# TLayerManager.net
KiCad netlist of a schematic drawn in Altium Designer
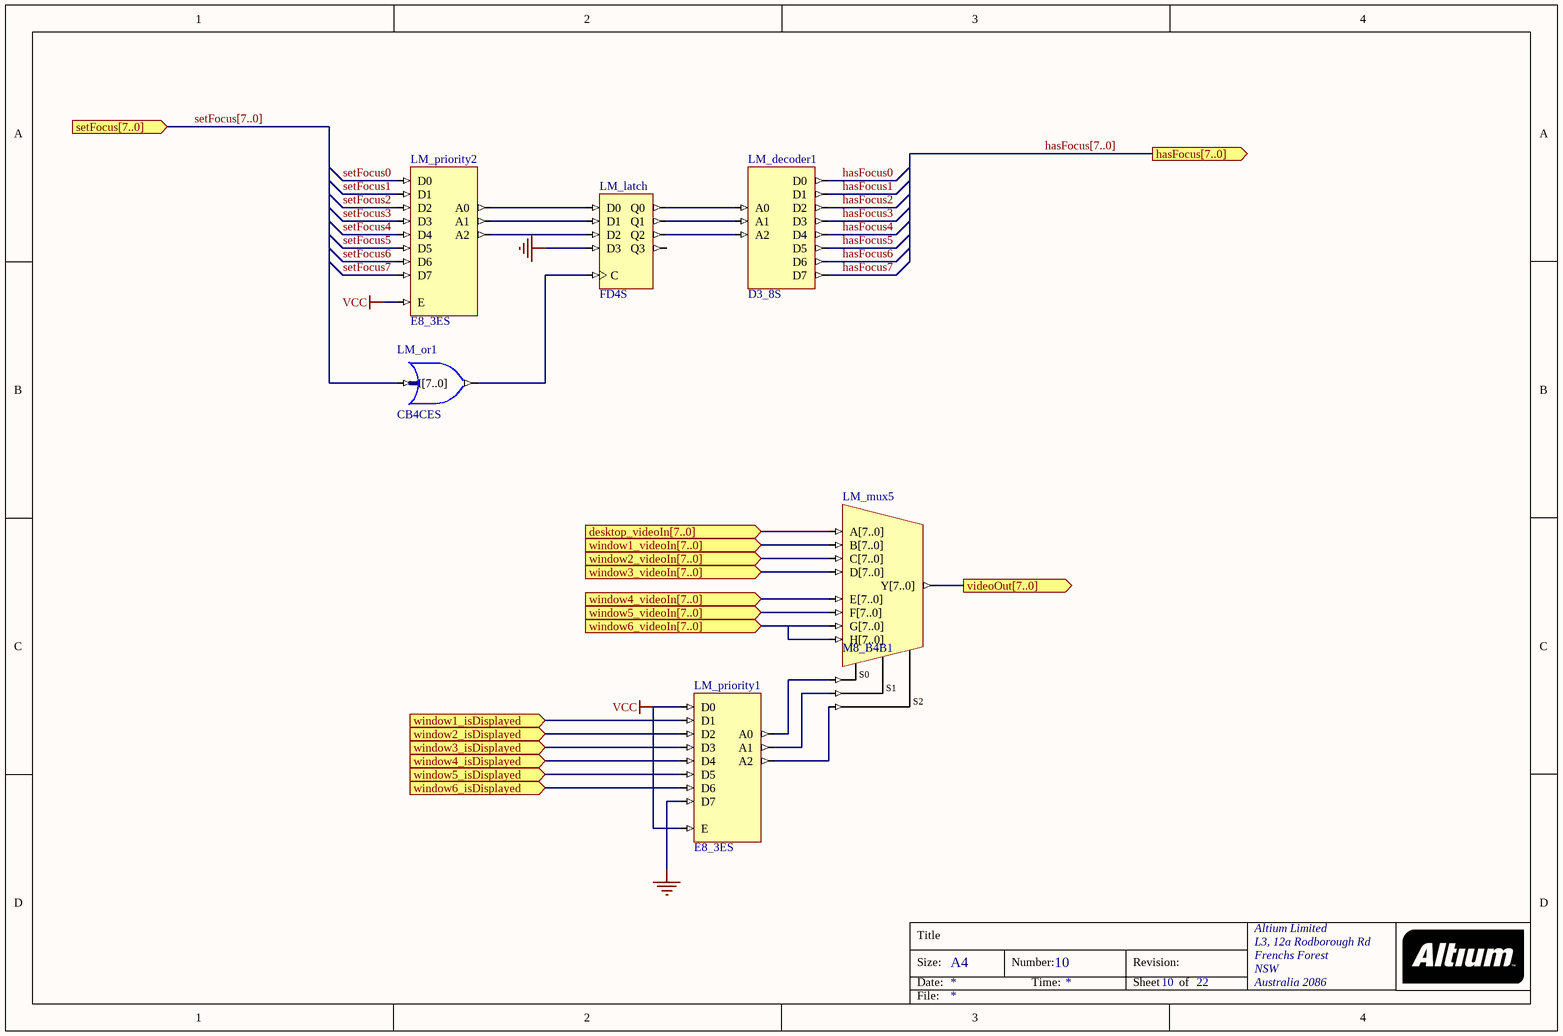
[diagram p0: TLayerManager.schDoc]

(export (version "E")
  (design (tool "Eeschema 10.0.6"))
  (components
    (comp (ref "LM_decoder1")
      (value "D3_8S")
      (description "Binary 3- to 8-Bit Decoder, Single Pin Version")
      (fields (field (name "PUBLISHER") "Altium Limited"))
      (libsource (lib "FPGA Generic") (part "D3_8S"))
    )
    (comp (ref "LM_latch")
      (value "FD4S")
      (description "4-Bit D-Type Flip-Flop, Single Pin Version")
      (fields (field (name "PUBLISHER") "Altium Limited"))
      (libsource (lib "FPGA Generic") (part "FD4S"))
    )
    (comp (ref "LM_mux5")
      (value "M8_B4B1")
      (description "8x8-Bit Bus to 1x8-Bit Bus Multiplexer")
      (fields (field (name "PUBLISHER") "Altium Limited"))
      (libsource (lib "FPGA Generic") (part "M8_B8B1"))
    )
    (comp (ref "LM_or1")
      (value "CB4CES")
      (description "8-Input OR Gate, Bus Version")
      (fields (field (name "PUBLISHER") "Altium Limited"))
      (libsource (lib "FPGA Generic") (part "OR8B"))
    )
    (comp (ref "LM_priority1")
      (value "E8_3ES")
      (description "8- to 3-Bit Priority Encoder with Enable, Single Pin Version")
      (fields (field (name "PUBLISHER") "Altium Limited"))
      (libsource (lib "FPGA Generic") (part "E8_3ES"))
    )
    (comp (ref "LM_priority2")
      (value "E8_3ES")
      (description "8- to 3-Bit Priority Encoder with Enable, Single Pin Version")
      (fields (field (name "PUBLISHER") "Altium Limited"))
      (libsource (lib "FPGA Generic") (part "E8_3ES"))
    )
  )
  (nets
    (net (code "65") (name "/desktop_videoIn[7..0]") (class "Default")
      (node (ref "LM_mux5") (pin "A[7..0]") (pinfunction "A[7..0]_A[7..0]") (pintype "input"))
    )
    (net (code "66") (name "/hasFocus0") (class "Default")
      (node (ref "LM_decoder1") (pin "D0") (pinfunction "D0_D0") (pintype "output"))
    )
    (net (code "67") (name "/hasFocus1") (class "Default")
      (node (ref "LM_decoder1") (pin "D1") (pinfunction "D1_D1") (pintype "output"))
    )
    (net (code "68") (name "/hasFocus2") (class "Default")
      (node (ref "LM_decoder1") (pin "D2") (pinfunction "D2_D2") (pintype "output"))
    )
    (net (code "69") (name "/hasFocus3") (class "Default")
      (node (ref "LM_decoder1") (pin "D3") (pinfunction "D3_D3") (pintype "output"))
    )
    (net (code "70") (name "/hasFocus4") (class "Default")
      (node (ref "LM_decoder1") (pin "D4") (pinfunction "D4_D4") (pintype "output"))
    )
    (net (code "71") (name "/hasFocus5") (class "Default")
      (node (ref "LM_decoder1") (pin "D5") (pinfunction "D5_D5") (pintype "output"))
    )
    (net (code "72") (name "/hasFocus6") (class "Default")
      (node (ref "LM_decoder1") (pin "D6") (pinfunction "D6_D6") (pintype "output"))
    )
    (net (code "73") (name "/hasFocus7") (class "Default")
      (node (ref "LM_decoder1") (pin "D7") (pinfunction "D7_D7") (pintype "output"))
    )
    (net (code "75") (name "/setFocus0") (class "Default")
      (node (ref "LM_priority2") (pin "D0") (pinfunction "D0_D0") (pintype "input"))
    )
    (net (code "76") (name "/setFocus1") (class "Default")
      (node (ref "LM_priority2") (pin "D1") (pinfunction "D1_D1") (pintype "input"))
    )
    (net (code "77") (name "/setFocus2") (class "Default")
      (node (ref "LM_priority2") (pin "D2") (pinfunction "D2_D2") (pintype "input"))
    )
    (net (code "78") (name "/setFocus3") (class "Default")
      (node (ref "LM_priority2") (pin "D3") (pinfunction "D3_D3") (pintype "input"))
    )
    (net (code "79") (name "/setFocus4") (class "Default")
      (node (ref "LM_priority2") (pin "D4") (pinfunction "D4_D4") (pintype "input"))
    )
    (net (code "80") (name "/setFocus5") (class "Default")
      (node (ref "LM_priority2") (pin "D5") (pinfunction "D5_D5") (pintype "input"))
    )
    (net (code "81") (name "/setFocus6") (class "Default")
      (node (ref "LM_priority2") (pin "D6") (pinfunction "D6_D6") (pintype "input"))
    )
    (net (code "82") (name "/setFocus7") (class "Default")
      (node (ref "LM_priority2") (pin "D7") (pinfunction "D7_D7") (pintype "input"))
    )
    (net (code "83") (name "/setFocus[7..0]") (class "Default")
      (node (ref "LM_or1") (pin "I[7..0]") (pinfunction "I[7..0]_I[7..0]") (pintype "input"))
    )
    (net (code "84") (name "/videoOut[7..0]") (class "Default")
      (node (ref "LM_mux5") (pin "Y[7..0]") (pinfunction "Y[7..0]_Y[7..0]") (pintype "output"))
    )
    (net (code "85") (name "/window1_isDisplayed") (class "Default")
      (node (ref "LM_priority1") (pin "D1") (pinfunction "D1_D1") (pintype "input"))
    )
    (net (code "86") (name "/window1_videoIn[7..0]") (class "Default")
      (node (ref "LM_mux5") (pin "B[7..0]") (pinfunction "B[7..0]_B[7..0]") (pintype "input"))
    )
    (net (code "87") (name "/window2_isDisplayed") (class "Default")
      (node (ref "LM_priority1") (pin "D2") (pinfunction "D2_D2") (pintype "input"))
    )
    (net (code "88") (name "/window2_videoIn[7..0]") (class "Default")
      (node (ref "LM_mux5") (pin "C[7..0]") (pinfunction "C[7..0]_C[7..0]") (pintype "input"))
    )
    (net (code "89") (name "/window3_isDisplayed") (class "Default")
      (node (ref "LM_priority1") (pin "D3") (pinfunction "D3_D3") (pintype "input"))
    )
    (net (code "90") (name "/window3_videoIn[7..0]") (class "Default")
      (node (ref "LM_mux5") (pin "D[7..0]") (pinfunction "D[7..0]_D[7..0]") (pintype "input"))
    )
    (net (code "91") (name "/window4_isDisplayed") (class "Default")
      (node (ref "LM_priority1") (pin "D4") (pinfunction "D4_D4") (pintype "input"))
    )
    (net (code "92") (name "/window4_videoIn[7..0]") (class "Default")
      (node (ref "LM_mux5") (pin "E[7..0]") (pinfunction "E[7..0]_E[7..0]") (pintype "input"))
    )
    (net (code "93") (name "/window5_isDisplayed") (class "Default")
      (node (ref "LM_priority1") (pin "D5") (pinfunction "D5_D5") (pintype "input"))
    )
    (net (code "94") (name "/window5_videoIn[7..0]") (class "Default")
      (node (ref "LM_mux5") (pin "F[7..0]") (pinfunction "F[7..0]_F[7..0]") (pintype "input"))
    )
    (net (code "95") (name "/window6_isDisplayed") (class "Default")
      (node (ref "LM_priority1") (pin "D6") (pinfunction "D6_D6") (pintype "input"))
    )
    (net (code "96") (name "/window6_videoIn[7..0]") (class "Default")
      (node (ref "LM_mux5") (pin "G[7..0]") (pinfunction "G[7..0]_G[7..0]") (pintype "input"))
    )
    (net (code "97") (name "GND") (class "Default")
      (node (ref "LM_latch") (pin "D3") (pinfunction "D3_D3") (pintype "input"))
      (node (ref "LM_priority1") (pin "D7") (pinfunction "D7_D7") (pintype "input"))
    )
    (net (code "98") (name "Net-(LM_decoder1-PadA0)") (class "Default")
      (node (ref "LM_decoder1") (pin "A0") (pinfunction "A0_A0") (pintype "input"))
      (node (ref "LM_latch") (pin "Q0") (pinfunction "Q0_Q0") (pintype "output"))
    )
    (net (code "99") (name "Net-(LM_decoder1-PadA1)") (class "Default")
      (node (ref "LM_decoder1") (pin "A1") (pinfunction "A1_A1") (pintype "input"))
      (node (ref "LM_latch") (pin "Q1") (pinfunction "Q1_Q1") (pintype "output"))
    )
    (net (code "100") (name "Net-(LM_decoder1-PadA2)") (class "Default")
      (node (ref "LM_decoder1") (pin "A2") (pinfunction "A2_A2") (pintype "input"))
      (node (ref "LM_latch") (pin "Q2") (pinfunction "Q2_Q2") (pintype "output"))
    )
    (net (code "101") (name "Net-(LM_latch-PadC)") (class "Default")
      (node (ref "LM_latch") (pin "C") (pinfunction "C_C") (pintype "input"))
      (node (ref "LM_or1") (pin "O") (pinfunction "O_O") (pintype "output"))
    )
    (net (code "102") (name "Net-(LM_latch-PadD0)") (class "Default")
      (node (ref "LM_latch") (pin "D0") (pinfunction "D0_D0") (pintype "input"))
      (node (ref "LM_priority2") (pin "A0") (pinfunction "A0_A0") (pintype "output"))
    )
    (net (code "103") (name "Net-(LM_latch-PadD1)") (class "Default")
      (node (ref "LM_latch") (pin "D1") (pinfunction "D1_D1") (pintype "input"))
      (node (ref "LM_priority2") (pin "A1") (pinfunction "A1_A1") (pintype "output"))
    )
    (net (code "104") (name "Net-(LM_latch-PadD2)") (class "Default")
      (node (ref "LM_latch") (pin "D2") (pinfunction "D2_D2") (pintype "input"))
      (node (ref "LM_priority2") (pin "A2") (pinfunction "A2_A2") (pintype "output"))
    )
    (net (code "105") (name "Net-(LM_mux5-PadS0)") (class "Default")
      (node (ref "LM_mux5") (pin "S0") (pinfunction "S0_S0") (pintype "input"))
      (node (ref "LM_priority1") (pin "A0") (pinfunction "A0_A0") (pintype "output"))
    )
    (net (code "106") (name "Net-(LM_mux5-PadS1)") (class "Default")
      (node (ref "LM_mux5") (pin "S1") (pinfunction "S1_S1") (pintype "input"))
      (node (ref "LM_priority1") (pin "A1") (pinfunction "A1_A1") (pintype "output"))
    )
    (net (code "107") (name "Net-(LM_mux5-PadS2)") (class "Default")
      (node (ref "LM_mux5") (pin "S2") (pinfunction "S2_S2") (pintype "input"))
      (node (ref "LM_priority1") (pin "A2") (pinfunction "A2_A2") (pintype "output"))
    )
    (net (code "108") (name "VCC") (class "Default")
      (node (ref "LM_priority1") (pin "D0") (pinfunction "D0_D0") (pintype "input"))
      (node (ref "LM_priority1") (pin "E") (pinfunction "E_E") (pintype "input"))
      (node (ref "LM_priority2") (pin "E") (pinfunction "E_E") (pintype "input"))
    )
    (net (code "109") (name "unconnected-(LM_latch-PadQ3)") (class "Default")
      (node (ref "LM_latch") (pin "Q3") (pinfunction "Q3_Q3") (pintype "output"))
    )
    (net (code "110") (name "unconnected-(LM_mux5-PadH[7..0])") (class "Default")
      (node (ref "LM_mux5") (pin "H[7..0]") (pinfunction "H[7..0]_H[7..0]") (pintype "input"))
    )
  )
)
